# USB-UART_FTDI_FT230XS.net
KiCad netlist of a schematic drawn in Altium Designer
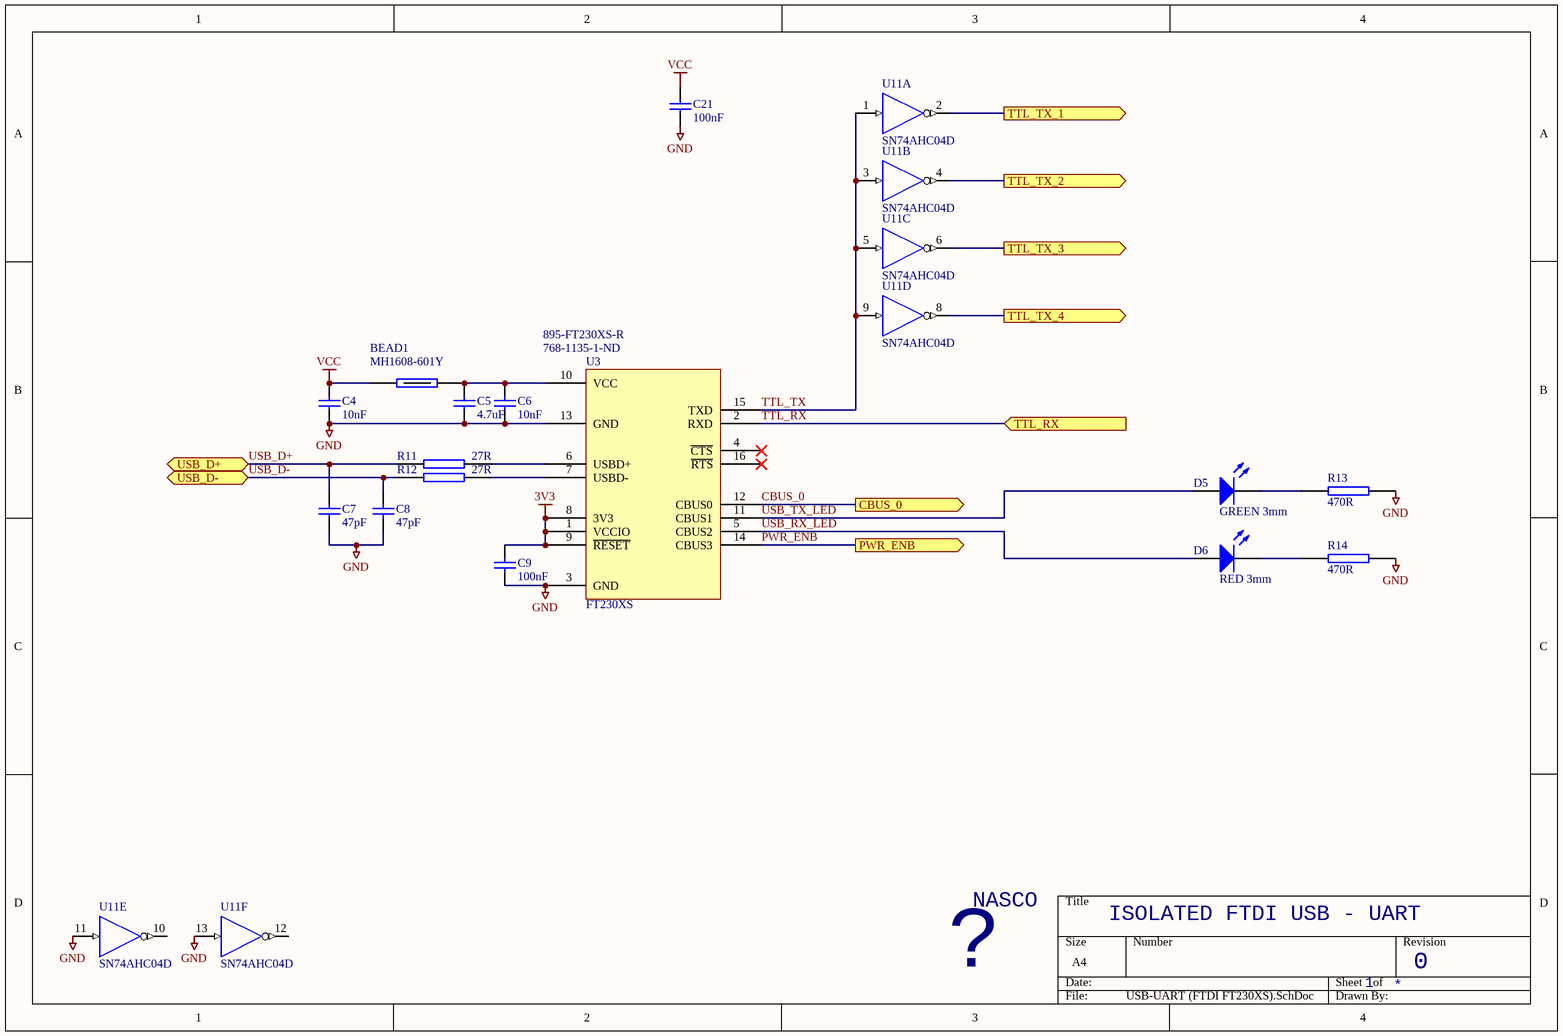
[diagram p0: USB-UART (FTDI FT230XS).SchDoc]

(export (version "E")
  (design (tool "Eeschema 10.0.6"))
  (components
    (comp (ref "BEAD1")
      (value "MH1608-601Y")
      (footprint "RES (3D) - 0603")
      (description "FERRITE BEAD 0603 BOURNS MH1608-601Y")
      (libsource (lib "Schlib1") (part "FERRITE BEAD 0603"))
    )
    (comp (ref "C4")
      (value "10nF")
      (footprint "CAP (3D) - 0603")
      (description "Capacitor")
      (libsource (lib "Miscellaneous Devices") (part "Cap"))
    )
    (comp (ref "C5")
      (value "4.7uF")
      (footprint "CAP ELECTRO SIZE-C")
      (description "Capacitor")
      (libsource (lib "Miscellaneous Devices") (part "Cap"))
    )
    (comp (ref "C6")
      (value "10nF")
      (footprint "CAP (3D) - 0603")
      (description "Capacitor")
      (libsource (lib "Miscellaneous Devices") (part "Cap"))
    )
    (comp (ref "C7")
      (value "47pF")
      (footprint "CAP (3D) - 0603")
      (description "Capacitor")
      (libsource (lib "Miscellaneous Devices") (part "Cap"))
    )
    (comp (ref "C8")
      (value "47pF")
      (footprint "CAP (3D) - 0603")
      (description "Capacitor")
      (libsource (lib "Miscellaneous Devices") (part "Cap"))
    )
    (comp (ref "C9")
      (value "100nF")
      (footprint "CAP (3D) - 0603")
      (description "Capacitor")
      (libsource (lib "Miscellaneous Devices") (part "Cap"))
    )
    (comp (ref "C21")
      (value "100nF")
      (footprint "CAP (3D) - 0603")
      (description "Capacitor")
      (libsource (lib "Miscellaneous Devices") (part "Cap"))
    )
    (comp (ref "D5")
      (value "GREEN 3mm")
      (footprint "LED(3D) 3MM RIGHT ANGLE GREEN")
      (description "3mm RED LED")
      (fields (field (name "MOUSER PART NO.") "604-WP132XIT") (field (name "FARNELL PART NO.") "1003393"))
      (libsource (lib "NASCO") (part "LED 3mm RED"))
    )
    (comp (ref "D6")
      (value "RED 3mm")
      (footprint "LED(3D) 3MM RIGHT ANGLE RED")
      (description "3mm RED LED")
      (fields (field (name "MOUSER PART NO.") "604-WP132XIT") (field (name "FARNELL PART NO.") "1003393"))
      (libsource (lib "NASCO") (part "LED 3mm RED"))
    )
    (comp (ref "R11")
      (value "27R")
      (footprint "RES (3D) - 0603")
      (description "RESISTOR SMD 0603")
      (libsource (lib "NASCO Resistors") (part "RES SMD 0603 100R"))
    )
    (comp (ref "R12")
      (value "27R")
      (footprint "RES (3D) - 0603")
      (description "RESISTOR SMD 0603")
      (libsource (lib "NASCO Resistors") (part "RES SMD 0603 100R"))
    )
    (comp (ref "R13")
      (value "470R")
      (footprint "RES (3D) - 0603")
      (description "RESISTOR SMD 0603 1k")
      (libsource (lib "NASCO Resistors") (part "RES SMD 0603 1k"))
    )
    (comp (ref "R14")
      (value "470R")
      (footprint "RES (3D) - 0603")
      (description "RESISTOR SMD 0603 1k")
      (libsource (lib "NASCO Resistors") (part "RES SMD 0603 1k"))
    )
    (comp (ref "U3")
      (value "FT230XS")
      (footprint "SSOP16_L")
      (description "FTDI FT230XS USB - UART")
      (fields
        (field (name "SUPPLIER PART NUMBER 1") "768-1135-1-ND")
        (field (name "SUPPLIER PART NUMBER 2") "895-FT230XS-R")
      )
      (libsource (lib "Schlib1") (part "FTDI FT230XS"))
    )
    (comp (ref "U11")
      (value "SN74AHC04D")
      (footprint "SOIC-14")
      (description "Hex Inverter")
      (fields (field (name "PUBLISHER") "Altium Limited"))
      (libsource (lib "TI Logic Gate 1") (part "SN74AHC04D"))
    )
  )
  (nets
    (net (code "1") (name "/CBUS_0") (class "Default")
      (node (ref "U3") (pin "12") (pinfunction "CBUS0_12") (pintype "passive"))
    )
    (net (code "2") (name "/PWR_ENB") (class "Default")
      (node (ref "U3") (pin "14") (pinfunction "CBUS3_14") (pintype "passive"))
    )
    (net (code "3") (name "/TTL_RX") (class "Default")
      (node (ref "U3") (pin "2") (pinfunction "RXD_2") (pintype "passive"))
    )
    (net (code "4") (name "/TTL_TX") (class "Default")
      (node (ref "U11") (pin "1") (pinfunction "A_1") (pintype "input"))
      (node (ref "U11") (pin "3") (pinfunction "A_3") (pintype "input"))
      (node (ref "U11") (pin "5") (pinfunction "A_5") (pintype "input"))
      (node (ref "U11") (pin "9") (pinfunction "A_9") (pintype "input"))
      (node (ref "U3") (pin "15") (pinfunction "TXD_15") (pintype "passive"))
    )
    (net (code "5") (name "/TTL_TX_1") (class "Default")
      (node (ref "U11") (pin "2") (pinfunction "Y_2") (pintype "output"))
    )
    (net (code "6") (name "/TTL_TX_2") (class "Default")
      (node (ref "U11") (pin "4") (pinfunction "Y_4") (pintype "output"))
    )
    (net (code "7") (name "/TTL_TX_3") (class "Default")
      (node (ref "U11") (pin "6") (pinfunction "Y_6") (pintype "output"))
    )
    (net (code "8") (name "/TTL_TX_4") (class "Default")
      (node (ref "U11") (pin "8") (pinfunction "Y_8") (pintype "output"))
    )
    (net (code "9") (name "/USB_D+") (class "Default")
      (node (ref "C7") (pin "2") (pinfunction "2_2") (pintype "passive"))
      (node (ref "R11") (pin "1") (pinfunction "1_1") (pintype "passive"))
    )
    (net (code "10") (name "/USB_D-") (class "Default")
      (node (ref "C8") (pin "2") (pinfunction "2_2") (pintype "passive"))
      (node (ref "R12") (pin "1") (pinfunction "1_1") (pintype "passive"))
    )
    (net (code "11") (name "/USB_RX_LED") (class "Default")
      (node (ref "D6") (pin "1") (pinfunction "A_1") (pintype "passive"))
      (node (ref "U3") (pin "5") (pinfunction "CBUS2_5") (pintype "passive"))
    )
    (net (code "12") (name "/USB_TX_LED") (class "Default")
      (node (ref "D5") (pin "1") (pinfunction "A_1") (pintype "passive"))
      (node (ref "U3") (pin "11") (pinfunction "CBUS1_11") (pintype "passive"))
    )
    (net (code "13") (name "3V3") (class "Default")
      (node (ref "C9") (pin "2") (pinfunction "2_2") (pintype "passive"))
      (node (ref "U3") (pin "1") (pinfunction "VCCIO_1") (pintype "passive"))
      (node (ref "U3") (pin "8") (pinfunction "3V3_8") (pintype "passive"))
      (node (ref "U3") (pin "9") (pinfunction "~{RESET}_9") (pintype "passive"))
    )
    (net (code "14") (name "GND") (class "Default")
      (node (ref "C21") (pin "1") (pinfunction "1_1") (pintype "passive"))
      (node (ref "C4") (pin "1") (pinfunction "1_1") (pintype "passive"))
      (node (ref "C5") (pin "2") (pinfunction "2_2") (pintype "passive"))
      (node (ref "C6") (pin "1") (pinfunction "1_1") (pintype "passive"))
      (node (ref "C7") (pin "1") (pinfunction "1_1") (pintype "passive"))
      (node (ref "C8") (pin "1") (pinfunction "1_1") (pintype "passive"))
      (node (ref "C9") (pin "1") (pinfunction "1_1") (pintype "passive"))
      (node (ref "R13") (pin "2") (pinfunction "2_2") (pintype "passive"))
      (node (ref "R14") (pin "2") (pinfunction "2_2") (pintype "passive"))
      (node (ref "U11") (pin "11") (pinfunction "A_11") (pintype "input"))
      (node (ref "U11") (pin "13") (pinfunction "A_13") (pintype "input"))
      (node (ref "U11") (pin "7") (pinfunction "GND_7") (pintype "power_in"))
      (node (ref "U3") (pin "13") (pinfunction "GND_13") (pintype "passive"))
      (node (ref "U3") (pin "3") (pinfunction "GND_3") (pintype "passive"))
    )
    (net (code "15") (name "Net-(D5-K)") (class "Default")
      (node (ref "D5") (pin "2") (pinfunction "K_2") (pintype "passive"))
      (node (ref "R13") (pin "1") (pinfunction "1_1") (pintype "passive"))
    )
    (net (code "16") (name "Net-(D6-K)") (class "Default")
      (node (ref "D6") (pin "2") (pinfunction "K_2") (pintype "passive"))
      (node (ref "R14") (pin "1") (pinfunction "1_1") (pintype "passive"))
    )
    (net (code "17") (name "Net-(U3-USBD+)") (class "Default")
      (node (ref "R11") (pin "2") (pinfunction "2_2") (pintype "passive"))
      (node (ref "U3") (pin "6") (pinfunction "USBD+_6") (pintype "passive"))
    )
    (net (code "18") (name "Net-(U3-USBD-)") (class "Default")
      (node (ref "R12") (pin "2") (pinfunction "2_2") (pintype "passive"))
      (node (ref "U3") (pin "7") (pinfunction "USBD-_7") (pintype "passive"))
    )
    (net (code "19") (name "Net-(U3-VCC)") (class "Default")
      (node (ref "BEAD1") (pin "2") (pinfunction "2_2") (pintype "passive"))
      (node (ref "C5") (pin "1") (pinfunction "1_1") (pintype "passive"))
      (node (ref "C6") (pin "2") (pinfunction "2_2") (pintype "passive"))
      (node (ref "U3") (pin "10") (pinfunction "VCC_10") (pintype "passive"))
    )
    (net (code "20") (name "VCC") (class "Default")
      (node (ref "BEAD1") (pin "1") (pinfunction "1_1") (pintype "passive"))
      (node (ref "C21") (pin "2") (pinfunction "2_2") (pintype "passive"))
      (node (ref "C4") (pin "2") (pinfunction "2_2") (pintype "passive"))
      (node (ref "U11") (pin "14") (pinfunction "VCC_14") (pintype "power_in"))
    )
    (net (code "21") (name "unconnected-(U3-~{CTS}-Pad4)") (class "Default")
      (node (ref "U3") (pin "4") (pinfunction "~{CTS}_4") (pintype "passive+no_connect"))
    )
    (net (code "22") (name "unconnected-(U3-~{RTS}-Pad16)") (class "Default")
      (node (ref "U3") (pin "16") (pinfunction "~{RTS}_16") (pintype "passive+no_connect"))
    )
    (net (code "23") (name "unconnected-(U11E-Y-Pad10)") (class "Default")
      (node (ref "U11") (pin "10") (pinfunction "Y_10") (pintype "output"))
    )
    (net (code "24") (name "unconnected-(U11F-Y-Pad12)") (class "Default")
      (node (ref "U11") (pin "12") (pinfunction "Y_12") (pintype "output"))
    )
  )
)
